# Master.net
KiCad netlist of a schematic drawn in EAGLE
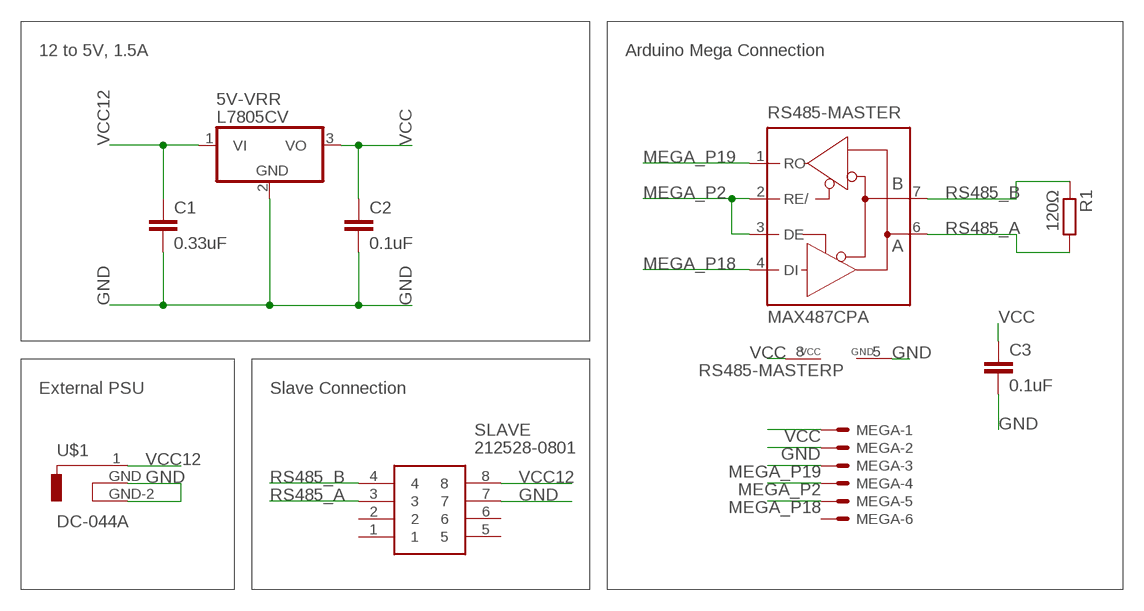
[diagram p0: schematic, sheet 1]

(export (version "E")
  (design (tool "Eeschema 10.0.6"))
  (components
    (comp (ref "5V-VRR")
      (value "L7805CV")
      (footprint "eagle-import:TO220H")
      (libsource (lib "eagle-import") (part "78T05"))
    )
    (comp (ref "C1")
      (value "0.33uF")
      (footprint "eagle-import:C025-025X050")
      (libsource (lib "eagle-import") (part "C-EU025-025X050"))
    )
    (comp (ref "C2")
      (value "0.1uF")
      (footprint "eagle-import:C025-025X050")
      (libsource (lib "eagle-import") (part "C-EU025-025X050"))
    )
    (comp (ref "C3")
      (value "0.1uF")
      (footprint "eagle-import:C025-025X050")
      (libsource (lib "eagle-import") (part "C-EU025-025X050"))
    )
    (comp (ref "MEGA")
      (value "22-23-2061")
      (footprint "eagle-import:22-23-2061")
      (fields (field (name "MF") "MOLEX"))
      (libsource (lib "eagle-import") (part "22-23-2061"))
    )
    (comp (ref "R1")
      (value "120Ω")
      (footprint "eagle-import:0207_10")
      (libsource (lib "eagle-import") (part "R-EU_0207/10"))
    )
    (comp (ref "RS485-MASTER")
      (value "MAX487CPA")
      (footprint "eagle-import:DIL08")
      (libsource (lib "eagle-import") (part "MAX487CPA"))
    )
    (comp (ref "SLAVE")
      (value "212528-0801")
      (footprint "eagle-import:212528-08YY")
      (fields (field (name "MOUSER_PART_NUMBER") "538-212528-0801"))
      (libsource (lib "eagle-import") (part "212528-0801"))
    )
    (comp (ref "U$1")
      (value "DC-044A")
      (footprint "eagle-import:DC-044A")
      (libsource (lib "eagle-import") (part "DC-044A"))
    )
  )
  (nets
    (net (code "1") (name "/GND") (class "Default")
      (node (ref "5V-VRR") (pin "2") (pinfunction "GND_2") (pintype "passive"))
      (node (ref "C1") (pin "2") (pinfunction "2_2") (pintype "passive"))
      (node (ref "C2") (pin "2") (pinfunction "2_2") (pintype "passive"))
      (node (ref "C3") (pin "2") (pinfunction "2_2") (pintype "passive"))
      (node (ref "MEGA") (pin "2") (pinfunction "S_2") (pintype "passive"))
      (node (ref "RS485-MASTER") (pin "5") (pinfunction "GND_5") (pintype "power_in"))
      (node (ref "SLAVE") (pin "7") (pinfunction "7_7") (pintype "bidirectional"))
      (node (ref "U$1") (pin "GND") (pinfunction "GND_GND") (pintype "power_in"))
      (node (ref "U$1") (pin "GND-2") (pinfunction "GND-2_GND-2") (pintype "power_in"))
    )
    (net (code "2") (name "/MEGA_P2") (class "Default")
      (node (ref "MEGA") (pin "4") (pinfunction "S_4") (pintype "passive"))
      (node (ref "RS485-MASTER") (pin "2") (pinfunction "RE/_2") (pintype "input"))
      (node (ref "RS485-MASTER") (pin "3") (pinfunction "DE_3") (pintype "input"))
    )
    (net (code "3") (name "/MEGA_P18") (class "Default")
      (node (ref "MEGA") (pin "5") (pinfunction "S_5") (pintype "passive"))
      (node (ref "RS485-MASTER") (pin "4") (pinfunction "DI_4") (pintype "input"))
    )
    (net (code "4") (name "/MEGA_P19") (class "Default")
      (node (ref "MEGA") (pin "3") (pinfunction "S_3") (pintype "passive"))
      (node (ref "RS485-MASTER") (pin "1") (pinfunction "RO_1") (pintype "output"))
    )
    (net (code "5") (name "/RS485_A") (class "Default")
      (node (ref "R1") (pin "2") (pinfunction "2_2") (pintype "passive"))
      (node (ref "RS485-MASTER") (pin "6") (pinfunction "A_6") (pintype "passive"))
      (node (ref "SLAVE") (pin "3") (pinfunction "3_3") (pintype "bidirectional"))
    )
    (net (code "6") (name "/RS485_B") (class "Default")
      (node (ref "R1") (pin "1") (pinfunction "1_1") (pintype "passive"))
      (node (ref "RS485-MASTER") (pin "7") (pinfunction "B_7") (pintype "passive"))
      (node (ref "SLAVE") (pin "4") (pinfunction "4_4") (pintype "bidirectional"))
    )
    (net (code "7") (name "/VCC") (class "Default")
      (node (ref "5V-VRR") (pin "3") (pinfunction "VO_3") (pintype "passive"))
      (node (ref "C2") (pin "1") (pinfunction "1_1") (pintype "passive"))
      (node (ref "C3") (pin "1") (pinfunction "1_1") (pintype "passive"))
      (node (ref "MEGA") (pin "1") (pinfunction "S_1") (pintype "passive"))
      (node (ref "RS485-MASTER") (pin "8") (pinfunction "VCC_8") (pintype "power_in"))
    )
    (net (code "8") (name "/VCC12") (class "Default")
      (node (ref "5V-VRR") (pin "1") (pinfunction "VI_1") (pintype "input"))
      (node (ref "C1") (pin "1") (pinfunction "1_1") (pintype "passive"))
      (node (ref "SLAVE") (pin "8") (pinfunction "8_8") (pintype "bidirectional"))
      (node (ref "U$1") (pin "1") (pinfunction "1_1") (pintype "power_in"))
    )
    (net (code "9") (name "unconnected-(MEGAF-S-Pad6)") (class "Default")
      (node (ref "MEGA") (pin "6") (pinfunction "S_6") (pintype "passive"))
    )
    (net (code "10") (name "unconnected-(SLAVE-Pad1)") (class "Default")
      (node (ref "SLAVE") (pin "1") (pinfunction "1_1") (pintype "bidirectional"))
    )
    (net (code "11") (name "unconnected-(SLAVE-Pad2)") (class "Default")
      (node (ref "SLAVE") (pin "2") (pinfunction "2_2") (pintype "bidirectional"))
    )
    (net (code "12") (name "unconnected-(SLAVE-Pad5)") (class "Default")
      (node (ref "SLAVE") (pin "5") (pinfunction "5_5") (pintype "bidirectional"))
    )
    (net (code "13") (name "unconnected-(SLAVE-Pad6)") (class "Default")
      (node (ref "SLAVE") (pin "6") (pinfunction "6_6") (pintype "bidirectional"))
    )
  )
)
